# mrna_badge.net
KiCad netlist of a schematic drawn in EAGLE
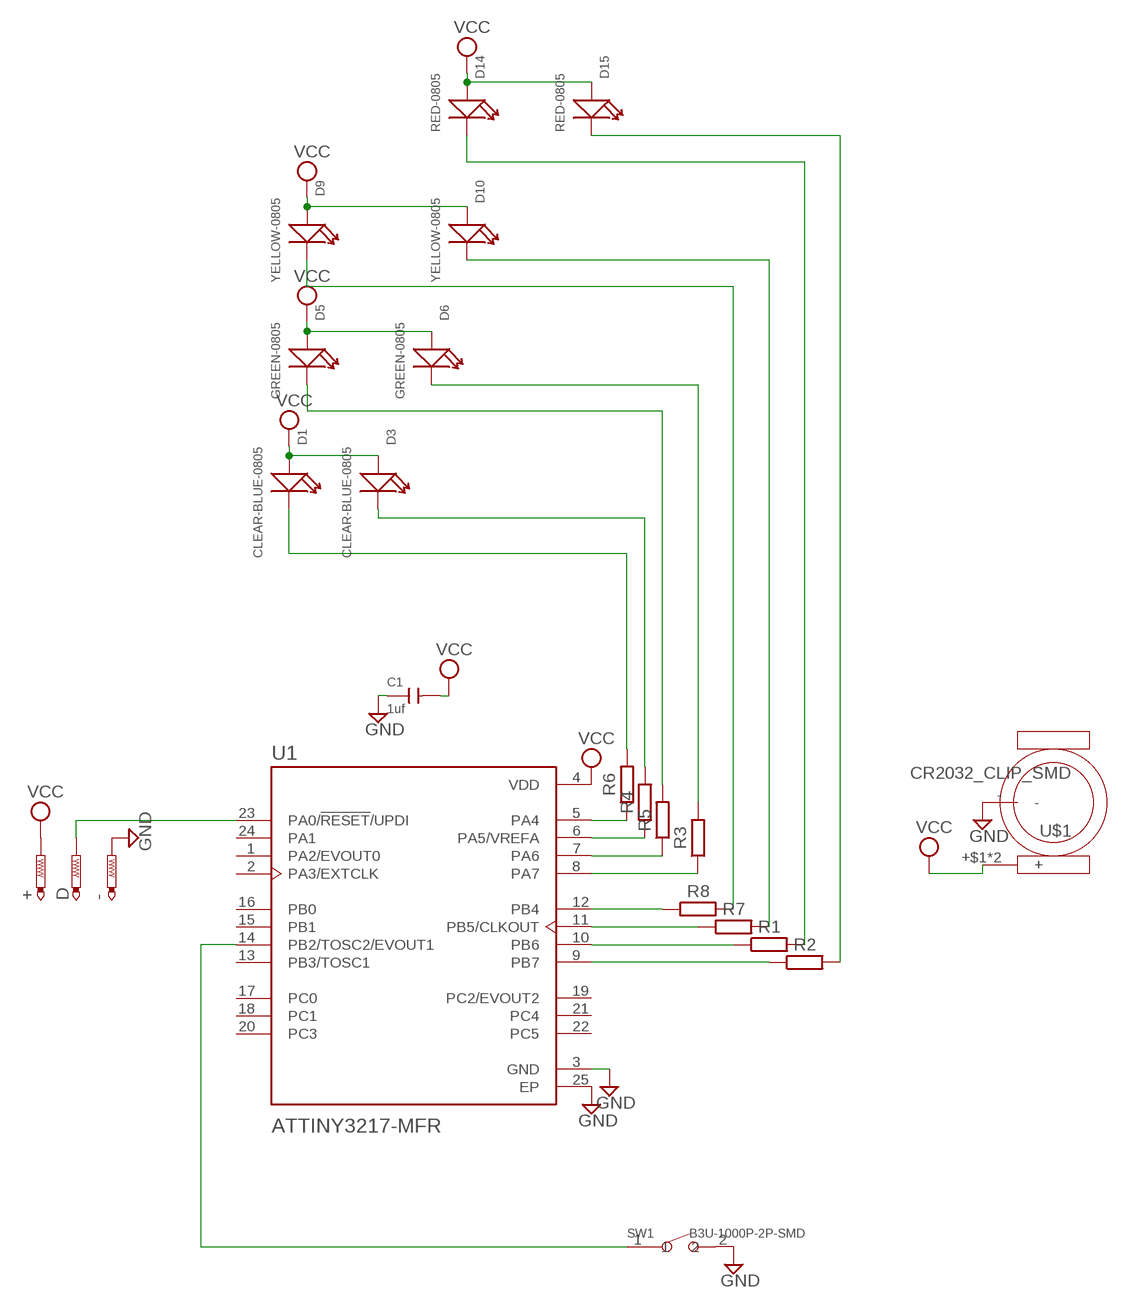
[diagram p0: schematic, sheet 1]

(export (version "E")
  (design (tool "Eeschema 10.0.6"))
  (components
    (comp (ref "+")
      (value "PTR1TP15R")
      (footprint "eagle-import:TP15R")
      (libsource (lib "eagle-import") (part "PTR1TP15R"))
    )
    (comp (ref "-")
      (value "PTR1TP15R")
      (footprint "eagle-import:TP15R")
      (libsource (lib "eagle-import") (part "PTR1TP15R"))
    )
    (comp (ref "C1")
      (value "1uf")
      (footprint "eagle-import:C0805")
      (fields (field (name "MPN") "CC0805KKX7R8BB105"))
      (libsource (lib "eagle-import") (part "CERAMIC-1UF-25V-10%-X7R(0805)"))
    )
    (comp (ref "D")
      (value "PTR1TP15R")
      (footprint "eagle-import:TP15R")
      (libsource (lib "eagle-import") (part "PTR1TP15R"))
    )
    (comp (ref "D1")
      (value "CLEAR-BLUE-0805")
      (footprint "eagle-import:LED-0805")
      (fields (field (name "MPN") "EL-17-215/BHC-AN1P2/3T"))
      (libsource (lib "eagle-import") (part "SMD-LED-CLEAR-BLUE(0805)"))
    )
    (comp (ref "D3")
      (value "CLEAR-BLUE-0805")
      (footprint "eagle-import:LED-0805")
      (fields (field (name "MPN") "EL-17-215/BHC-AN1P2/3T"))
      (libsource (lib "eagle-import") (part "SMD-LED-CLEAR-BLUE(0805)"))
    )
    (comp (ref "D5")
      (value "GREEN-0805")
      (footprint "eagle-import:LED-0805")
      (fields (field (name "MPN") "17-215SYGC/S530-E2/TR8"))
      (libsource (lib "eagle-import") (part "SMD-LED-CLEAR-GREEN(0805)"))
    )
    (comp (ref "D6")
      (value "GREEN-0805")
      (footprint "eagle-import:LED-0805")
      (fields (field (name "MPN") "17-215SYGC/S530-E2/TR8"))
      (libsource (lib "eagle-import") (part "SMD-LED-CLEAR-GREEN(0805)"))
    )
    (comp (ref "D9")
      (value "YELLOW-0805")
      (footprint "eagle-import:LED-0805")
      (fields (field (name "MPN") "17-215UYC/S530-A3/TR8"))
      (libsource (lib "eagle-import") (part "SMD-LED-CLEAR-YELLOW(0805)"))
    )
    (comp (ref "D10")
      (value "YELLOW-0805")
      (footprint "eagle-import:LED-0805")
      (fields (field (name "MPN") "17-215UYC/S530-A3/TR8"))
      (libsource (lib "eagle-import") (part "SMD-LED-CLEAR-YELLOW(0805)"))
    )
    (comp (ref "D14")
      (value "RED-0805")
      (footprint "eagle-import:LED-0805")
      (fields (field (name "MPN") "17-215SURC/S530-A2/TR8"))
      (libsource (lib "eagle-import") (part "SMD-LED-CLEAR-RED(0805)"))
    )
    (comp (ref "D15")
      (value "RED-0805")
      (footprint "eagle-import:LED-0805")
      (fields (field (name "MPN") "17-215SURC/S530-A2/TR8"))
      (libsource (lib "eagle-import") (part "SMD-LED-CLEAR-RED(0805)"))
    )
    (comp (ref "R1")
      (value "R_CHIP-0805(2012-METRIC)")
      (footprint "eagle-import:RESC2012X65")
      (libsource (lib "eagle-import") (part "RCHIP-0805(2012-METRIC)_"))
    )
    (comp (ref "R2")
      (value "R_CHIP-0805(2012-METRIC)")
      (footprint "eagle-import:RESC2012X65")
      (libsource (lib "eagle-import") (part "RCHIP-0805(2012-METRIC)_"))
    )
    (comp (ref "R3")
      (value "R_CHIP-0805(2012-METRIC)")
      (footprint "eagle-import:RESC2012X65")
      (libsource (lib "eagle-import") (part "RCHIP-0805(2012-METRIC)_"))
    )
    (comp (ref "R4")
      (value "R_CHIP-0805(2012-METRIC)")
      (footprint "eagle-import:RESC2012X65")
      (libsource (lib "eagle-import") (part "RCHIP-0805(2012-METRIC)_"))
    )
    (comp (ref "R5")
      (value "R_CHIP-0805(2012-METRIC)")
      (footprint "eagle-import:RESC2012X65")
      (libsource (lib "eagle-import") (part "RCHIP-0805(2012-METRIC)_"))
    )
    (comp (ref "R6")
      (value "R_CHIP-0805(2012-METRIC)")
      (footprint "eagle-import:RESC2012X65")
      (libsource (lib "eagle-import") (part "RCHIP-0805(2012-METRIC)_"))
    )
    (comp (ref "R7")
      (value "R_CHIP-0805(2012-METRIC)")
      (footprint "eagle-import:RESC2012X65")
      (libsource (lib "eagle-import") (part "RCHIP-0805(2012-METRIC)_"))
    )
    (comp (ref "R8")
      (value "R_CHIP-0805(2012-METRIC)")
      (footprint "eagle-import:RESC2012X65")
      (libsource (lib "eagle-import") (part "RCHIP-0805(2012-METRIC)_"))
    )
    (comp (ref "SW1")
      (value "B3U-1000P-2P-SMD")
      (footprint "eagle-import:SW2-2.6-3.0X2.5X1.2+0.4MM")
      (libsource (lib "eagle-import") (part "SMD-BUTTON(2P-3.0X2.5X1.2+0.4MM)-B3U-1000P-2P-SMD"))
    )
    (comp (ref "U$1")
      (value "CR2032_CLIP_SMD")
      (footprint "eagle-import:CR2032_SMT_BAT-HLD-001")
      (libsource (lib "eagle-import") (part "CR2032_CLIP_SMD"))
    )
    (comp (ref "U1")
      (value "ATTINY3217-MFR")
      (footprint "eagle-import:QFN50P400X400X90-25N")
      (fields (field (name "MF") "Microchip"))
      (libsource (lib "eagle-import") (part "ATTINY3217-MFR"))
    )
  )
  (nets
    (net (code "1") (name "GND") (class "Default")
      (node (ref "-") (pin "TP") (pinfunction "TP_TP") (pintype "input"))
      (node (ref "C1") (pin "1") (pinfunction "1_1") (pintype "passive"))
      (node (ref "SW1") (pin "2") (pinfunction "2_2") (pintype "bidirectional"))
      (node (ref "U$1") (pin "-") (pinfunction "-_-") (pintype "bidirectional"))
      (node (ref "U1") (pin "25") (pinfunction "EP_25") (pintype "power_in"))
      (node (ref "U1") (pin "3") (pinfunction "GND_3") (pintype "power_in"))
    )
    (net (code "2") (name "Net-(D1-Pad-)") (class "Default")
      (node (ref "D1") (pin "-") (pinfunction "-_-") (pintype "passive"))
      (node (ref "R6") (pin "2") (pinfunction "2_2") (pintype "passive"))
    )
    (net (code "3") (name "Net-(D3-Pad-)") (class "Default")
      (node (ref "D3") (pin "-") (pinfunction "-_-") (pintype "passive"))
      (node (ref "R4") (pin "2") (pinfunction "2_2") (pintype "passive"))
    )
    (net (code "4") (name "Net-(D5-Pad-)") (class "Default")
      (node (ref "D5") (pin "-") (pinfunction "-_-") (pintype "passive"))
      (node (ref "R5") (pin "2") (pinfunction "2_2") (pintype "passive"))
    )
    (net (code "5") (name "Net-(D6-Pad-)") (class "Default")
      (node (ref "D6") (pin "-") (pinfunction "-_-") (pintype "passive"))
      (node (ref "R3") (pin "2") (pinfunction "2_2") (pintype "passive"))
    )
    (net (code "6") (name "Net-(D9-Pad-)") (class "Default")
      (node (ref "D9") (pin "-") (pinfunction "-_-") (pintype "passive"))
      (node (ref "R8") (pin "2") (pinfunction "2_2") (pintype "passive"))
    )
    (net (code "7") (name "Net-(D10-Pad-)") (class "Default")
      (node (ref "D10") (pin "-") (pinfunction "-_-") (pintype "passive"))
      (node (ref "R7") (pin "2") (pinfunction "2_2") (pintype "passive"))
    )
    (net (code "8") (name "Net-(D14-Pad-)") (class "Default")
      (node (ref "D14") (pin "-") (pinfunction "-_-") (pintype "passive"))
      (node (ref "R1") (pin "2") (pinfunction "2_2") (pintype "passive"))
    )
    (net (code "9") (name "Net-(D15-Pad-)") (class "Default")
      (node (ref "D15") (pin "-") (pinfunction "-_-") (pintype "passive"))
      (node (ref "R2") (pin "2") (pinfunction "2_2") (pintype "passive"))
    )
    (net (code "10") (name "Net-(U1-PA0{slash}~{RESET}{slash}UPDI)") (class "Default")
      (node (ref "D") (pin "TP") (pinfunction "TP_TP") (pintype "input"))
      (node (ref "U1") (pin "23") (pinfunction "PA0/~{RESET}/UPDI_23") (pintype "bidirectional"))
    )
    (net (code "11") (name "Net-(U1-PA4)") (class "Default")
      (node (ref "R6") (pin "1") (pinfunction "1_1") (pintype "passive"))
      (node (ref "U1") (pin "5") (pinfunction "PA4_5") (pintype "bidirectional"))
    )
    (net (code "12") (name "Net-(U1-PA5{slash}VREFA)") (class "Default")
      (node (ref "R4") (pin "1") (pinfunction "1_1") (pintype "passive"))
      (node (ref "U1") (pin "6") (pinfunction "PA5/VREFA_6") (pintype "bidirectional"))
    )
    (net (code "13") (name "Net-(U1-PA6)") (class "Default")
      (node (ref "R5") (pin "1") (pinfunction "1_1") (pintype "passive"))
      (node (ref "U1") (pin "7") (pinfunction "PA6_7") (pintype "bidirectional"))
    )
    (net (code "14") (name "Net-(U1-PA7)") (class "Default")
      (node (ref "R3") (pin "1") (pinfunction "1_1") (pintype "passive"))
      (node (ref "U1") (pin "8") (pinfunction "PA7_8") (pintype "bidirectional"))
    )
    (net (code "15") (name "Net-(U1-PB2{slash}TOSC2{slash}EVOUT1)") (class "Default")
      (node (ref "SW1") (pin "1") (pinfunction "1_1") (pintype "bidirectional"))
      (node (ref "U1") (pin "14") (pinfunction "PB2/TOSC2/EVOUT1_14") (pintype "bidirectional"))
    )
    (net (code "16") (name "Net-(U1-PB4)") (class "Default")
      (node (ref "R8") (pin "1") (pinfunction "1_1") (pintype "passive"))
      (node (ref "U1") (pin "12") (pinfunction "PB4_12") (pintype "bidirectional"))
    )
    (net (code "17") (name "Net-(U1-PB5{slash}CLKOUT)") (class "Default")
      (node (ref "R7") (pin "1") (pinfunction "1_1") (pintype "passive"))
      (node (ref "U1") (pin "11") (pinfunction "PB5/CLKOUT_11") (pintype "bidirectional"))
    )
    (net (code "18") (name "Net-(U1-PB6)") (class "Default")
      (node (ref "R1") (pin "1") (pinfunction "1_1") (pintype "passive"))
      (node (ref "U1") (pin "10") (pinfunction "PB6_10") (pintype "bidirectional"))
    )
    (net (code "19") (name "Net-(U1-PB7)") (class "Default")
      (node (ref "R2") (pin "1") (pinfunction "1_1") (pintype "passive"))
      (node (ref "U1") (pin "9") (pinfunction "PB7_9") (pintype "bidirectional"))
    )
    (net (code "20") (name "VCC") (class "Default")
      (node (ref "+") (pin "TP") (pinfunction "TP_TP") (pintype "input"))
      (node (ref "C1") (pin "2") (pinfunction "2_2") (pintype "passive"))
      (node (ref "D1") (pin "+") (pinfunction "+_+") (pintype "passive"))
      (node (ref "D10") (pin "+") (pinfunction "+_+") (pintype "passive"))
      (node (ref "D14") (pin "+") (pinfunction "+_+") (pintype "passive"))
      (node (ref "D15") (pin "+") (pinfunction "+_+") (pintype "passive"))
      (node (ref "D3") (pin "+") (pinfunction "+_+") (pintype "passive"))
      (node (ref "D5") (pin "+") (pinfunction "+_+") (pintype "passive"))
      (node (ref "D6") (pin "+") (pinfunction "+_+") (pintype "passive"))
      (node (ref "D9") (pin "+") (pinfunction "+_+") (pintype "passive"))
      (node (ref "U$1") (pin "+$1") (pinfunction "+_+$1") (pintype "bidirectional"))
      (node (ref "U$1") (pin "+$2") (pinfunction "+_+$2") (pintype "bidirectional"))
      (node (ref "U1") (pin "4") (pinfunction "VDD_4") (pintype "power_in"))
    )
    (net (code "21") (name "unconnected-(U1-PA1-Pad24)") (class "Default")
      (node (ref "U1") (pin "24") (pinfunction "PA1_24") (pintype "bidirectional"))
    )
    (net (code "22") (name "unconnected-(U1-PA2{slash}EVOUT0-Pad1)") (class "Default")
      (node (ref "U1") (pin "1") (pinfunction "PA2/EVOUT0_1") (pintype "bidirectional"))
    )
    (net (code "23") (name "unconnected-(U1-PA3{slash}EXTCLK-Pad2)") (class "Default")
      (node (ref "U1") (pin "2") (pinfunction "PA3/EXTCLK_2") (pintype "bidirectional"))
    )
    (net (code "24") (name "unconnected-(U1-PB0-Pad16)") (class "Default")
      (node (ref "U1") (pin "16") (pinfunction "PB0_16") (pintype "bidirectional"))
    )
    (net (code "25") (name "unconnected-(U1-PB1-Pad15)") (class "Default")
      (node (ref "U1") (pin "15") (pinfunction "PB1_15") (pintype "bidirectional"))
    )
    (net (code "26") (name "unconnected-(U1-PB3{slash}TOSC1-Pad13)") (class "Default")
      (node (ref "U1") (pin "13") (pinfunction "PB3/TOSC1_13") (pintype "bidirectional"))
    )
    (net (code "27") (name "unconnected-(U1-PC0-Pad17)") (class "Default")
      (node (ref "U1") (pin "17") (pinfunction "PC0_17") (pintype "bidirectional"))
    )
    (net (code "28") (name "unconnected-(U1-PC1-Pad18)") (class "Default")
      (node (ref "U1") (pin "18") (pinfunction "PC1_18") (pintype "bidirectional"))
    )
    (net (code "29") (name "unconnected-(U1-PC2{slash}EVOUT2-Pad19)") (class "Default")
      (node (ref "U1") (pin "19") (pinfunction "PC2/EVOUT2_19") (pintype "bidirectional"))
    )
    (net (code "30") (name "unconnected-(U1-PC3-Pad20)") (class "Default")
      (node (ref "U1") (pin "20") (pinfunction "PC3_20") (pintype "bidirectional"))
    )
    (net (code "31") (name "unconnected-(U1-PC4-Pad21)") (class "Default")
      (node (ref "U1") (pin "21") (pinfunction "PC4_21") (pintype "bidirectional"))
    )
    (net (code "32") (name "unconnected-(U1-PC5-Pad22)") (class "Default")
      (node (ref "U1") (pin "22") (pinfunction "PC5_22") (pintype "bidirectional"))
    )
  )
)
